# waterius-factory.net
KiCad netlist of a schematic drawn in EAGLE
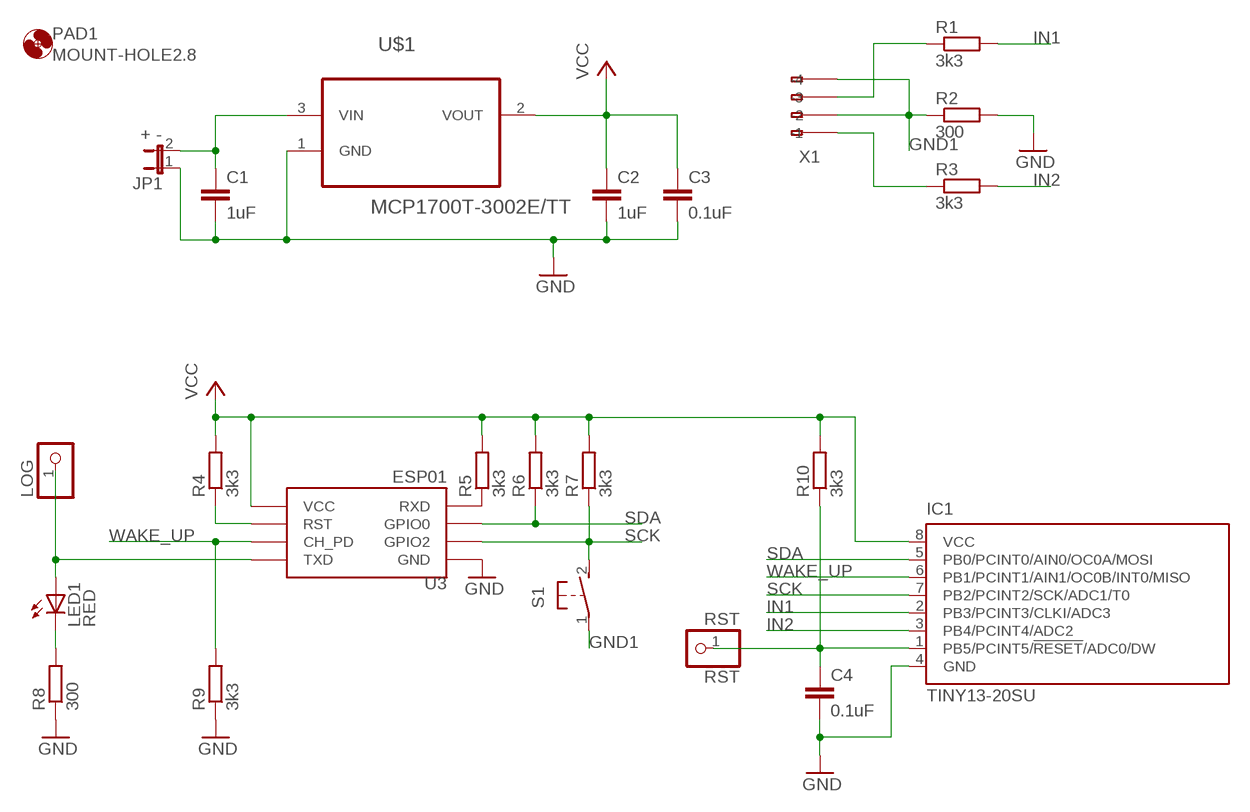
[diagram p0: schematic, sheet 1]

(export (version "E")
  (design (tool "Eeschema 10.0.6"))
  (components
    (comp (ref "C1")
      (value "1uF")
      (footprint "eagle-import:C0805")
      (libsource (lib "eagle-import") (part "C-EUC0805"))
    )
    (comp (ref "C2")
      (value "1uF")
      (footprint "eagle-import:C0805")
      (libsource (lib "eagle-import") (part "C-EUC0805"))
    )
    (comp (ref "C3")
      (value "0.1uF")
      (footprint "eagle-import:C0805")
      (libsource (lib "eagle-import") (part "C-EUC0805"))
    )
    (comp (ref "C4")
      (value "0.1uF")
      (footprint "eagle-import:C0805")
      (libsource (lib "eagle-import") (part "C-EUC0805"))
    )
    (comp (ref "IC1")
      (value "TINY13-20SU")
      (footprint "eagle-import:8S2")
      (fields (field (name "MPN") "ATTINY13-20SU"))
      (libsource (lib "eagle-import") (part "TINY13SU-20"))
    )
    (comp (ref "JP1")
      (value "+ -")
      (footprint "eagle-import:JP1")
      (libsource (lib "eagle-import") (part "JP1E"))
    )
    (comp (ref "LED1")
      (value "RED")
      (footprint "eagle-import:LED3MM")
      (libsource (lib "eagle-import") (part "LED3MM"))
    )
    (comp (ref "LOG")
      (value "PINHD-1X1")
      (footprint "eagle-import:1X01")
      (libsource (lib "eagle-import") (part "PINHD-1X1"))
    )
    (comp (ref "PAD1")
      (value "MOUNT-HOLE2.8")
      (footprint "eagle-import:2,8")
      (libsource (lib "eagle-import") (part "MOUNT-HOLE2.8"))
    )
    (comp (ref "R1")
      (value "3k3")
      (footprint "eagle-import:R0805")
      (libsource (lib "eagle-import") (part "R-EU_R0805"))
    )
    (comp (ref "R2")
      (value "300")
      (footprint "eagle-import:R0805")
      (libsource (lib "eagle-import") (part "R-EU_R0805"))
    )
    (comp (ref "R3")
      (value "3k3")
      (footprint "eagle-import:R0805")
      (libsource (lib "eagle-import") (part "R-EU_R0805"))
    )
    (comp (ref "R4")
      (value "3k3")
      (footprint "eagle-import:R0805")
      (libsource (lib "eagle-import") (part "R-EU_R0805"))
    )
    (comp (ref "R5")
      (value "3k3")
      (footprint "eagle-import:R0805")
      (libsource (lib "eagle-import") (part "R-EU_R0805"))
    )
    (comp (ref "R6")
      (value "3k3")
      (footprint "eagle-import:R0805")
      (libsource (lib "eagle-import") (part "R-EU_R0805"))
    )
    (comp (ref "R7")
      (value "3k3")
      (footprint "eagle-import:R0805")
      (libsource (lib "eagle-import") (part "R-EU_R0805"))
    )
    (comp (ref "R8")
      (value "300")
      (footprint "eagle-import:R0805")
      (libsource (lib "eagle-import") (part "R-EU_R0805"))
    )
    (comp (ref "R9")
      (value "3k3")
      (footprint "eagle-import:R0805")
      (libsource (lib "eagle-import") (part "R-EU_R0805"))
    )
    (comp (ref "R10")
      (value "3k3")
      (footprint "eagle-import:R0805")
      (libsource (lib "eagle-import") (part "R-EU_R0805"))
    )
    (comp (ref "RST")
      (value "RST")
      (footprint "eagle-import:1X01")
      (libsource (lib "eagle-import") (part "PINHD-1X1"))
    )
    (comp (ref "S1")
      (value "31-XX")
      (footprint "eagle-import:B3F-31XX")
      (fields (field (name "MPN") "B3F-3100"))
      (libsource (lib "eagle-import") (part "31-XX"))
    )
    (comp (ref "U$1")
      (value "MCP1700T-3002E/TT")
      (footprint "eagle-import:SOT95P237X112-3N")
      (libsource (lib "eagle-import") (part "MCP1700T-3002E/TT"))
    )
    (comp (ref "U3")
      (value "ESP01")
      (footprint "eagle-import:ESP01")
      (libsource (lib "eagle-import") (part "ESP01"))
    )
    (comp (ref "X1")
      (value "233-104")
      (footprint "eagle-import:233-104")
      (libsource (lib "eagle-import") (part "233-104"))
    )
  )
  (nets
    (net (code "1") (name "/GND1") (class "Default")
      (node (ref "R2") (pin "1") (pinfunction "1_1") (pintype "passive"))
      (node (ref "S1") (pin "1") (pinfunction "P_1") (pintype "passive"))
      (node (ref "X1") (pin "A2") (pinfunction "-2_A2") (pintype "passive"))
      (node (ref "X1") (pin "A4") (pinfunction "-4_A4") (pintype "passive"))
    )
    (net (code "2") (name "/IN1") (class "Default")
      (node (ref "IC1") (pin "2") (pinfunction "PB3/PCINT3/CLKI/ADC3_2") (pintype "bidirectional"))
      (node (ref "R1") (pin "2") (pinfunction "2_2") (pintype "passive"))
    )
    (net (code "3") (name "/IN2") (class "Default")
      (node (ref "IC1") (pin "3") (pinfunction "PB4/PCINT4/ADC2_3") (pintype "bidirectional"))
      (node (ref "R3") (pin "2") (pinfunction "2_2") (pintype "passive"))
    )
    (net (code "4") (name "/SCK") (class "Default")
      (node (ref "IC1") (pin "7") (pinfunction "PB2/PCINT2/SCK/ADC1/T0_7") (pintype "bidirectional"))
      (node (ref "R7") (pin "1") (pinfunction "1_1") (pintype "passive"))
      (node (ref "S1") (pin "2") (pinfunction "S_2") (pintype "passive"))
      (node (ref "U3") (pin "GPIO2") (pinfunction "GPIO2_GPIO2") (pintype "bidirectional"))
    )
    (net (code "5") (name "/SDA") (class "Default")
      (node (ref "IC1") (pin "5") (pinfunction "PB0/PCINT0/AIN0/OC0A/MOSI_5") (pintype "bidirectional"))
      (node (ref "R6") (pin "1") (pinfunction "1_1") (pintype "passive"))
      (node (ref "U3") (pin "GPIO0") (pinfunction "GPIO0_GPIO0") (pintype "bidirectional"))
    )
    (net (code "6") (name "/WAKE_UP") (class "Default")
      (node (ref "IC1") (pin "6") (pinfunction "PB1/PCINT1/AIN1/OC0B/INT0/MISO_6") (pintype "bidirectional"))
      (node (ref "R9") (pin "2") (pinfunction "2_2") (pintype "passive"))
      (node (ref "U3") (pin "CH_PD") (pinfunction "CH_PD_CH_PD") (pintype "bidirectional"))
    )
    (net (code "7") (name "GND") (class "Default")
      (node (ref "C1") (pin "2") (pinfunction "2_2") (pintype "passive"))
      (node (ref "C2") (pin "2") (pinfunction "2_2") (pintype "passive"))
      (node (ref "C3") (pin "2") (pinfunction "2_2") (pintype "passive"))
      (node (ref "C4") (pin "2") (pinfunction "2_2") (pintype "passive"))
      (node (ref "IC1") (pin "4") (pinfunction "GND_4") (pintype "power_in"))
      (node (ref "JP1") (pin "1") (pinfunction "1_1") (pintype "passive"))
      (node (ref "R2") (pin "2") (pinfunction "2_2") (pintype "passive"))
      (node (ref "R8") (pin "1") (pinfunction "1_1") (pintype "passive"))
      (node (ref "R9") (pin "1") (pinfunction "1_1") (pintype "passive"))
      (node (ref "U$1") (pin "1") (pinfunction "GND_1") (pintype "passive"))
      (node (ref "U3") (pin "GND") (pinfunction "GND_GND") (pintype "bidirectional"))
    )
    (net (code "8") (name "Net-(IC1-PB5{slash}PCINT5{slash}~{RESET}{slash}ADC0{slash}DW)") (class "Default")
      (node (ref "C4") (pin "1") (pinfunction "1_1") (pintype "passive"))
      (node (ref "IC1") (pin "1") (pinfunction "PB5/PCINT5/~{RESET}/ADC0/DW_1") (pintype "bidirectional"))
      (node (ref "R10") (pin "1") (pinfunction "1_1") (pintype "passive"))
      (node (ref "RST") (pin "1") (pinfunction "1_1") (pintype "passive"))
    )
    (net (code "9") (name "Net-(LED1-C)") (class "Default")
      (node (ref "LED1") (pin "K") (pinfunction "C_K") (pintype "passive"))
      (node (ref "R8") (pin "2") (pinfunction "2_2") (pintype "passive"))
    )
    (net (code "10") (name "Net-(R4-Pad1)") (class "Default")
      (node (ref "R4") (pin "1") (pinfunction "1_1") (pintype "passive"))
      (node (ref "U3") (pin "RST") (pinfunction "RST_RST") (pintype "bidirectional"))
    )
    (net (code "11") (name "Net-(U$1-VIN)") (class "Default")
      (node (ref "C1") (pin "1") (pinfunction "1_1") (pintype "passive"))
      (node (ref "JP1") (pin "2") (pinfunction "2_2") (pintype "passive"))
      (node (ref "U$1") (pin "3") (pinfunction "VIN_3") (pintype "input"))
    )
    (net (code "12") (name "Net-(U3-RXD)") (class "Default")
      (node (ref "R5") (pin "1") (pinfunction "1_1") (pintype "passive"))
      (node (ref "U3") (pin "RX") (pinfunction "RXD_RX") (pintype "bidirectional"))
    )
    (net (code "13") (name "Net-(U3-TXD)") (class "Default")
      (node (ref "LED1") (pin "A") (pinfunction "A_A") (pintype "passive"))
      (node (ref "LOG") (pin "1") (pinfunction "1_1") (pintype "passive"))
      (node (ref "U3") (pin "TX") (pinfunction "TXD_TX") (pintype "bidirectional"))
    )
    (net (code "14") (name "Net-(X1--1)") (class "Default")
      (node (ref "R3") (pin "1") (pinfunction "1_1") (pintype "passive"))
      (node (ref "X1") (pin "A1") (pinfunction "-1_A1") (pintype "passive"))
    )
    (net (code "15") (name "Net-(X1--3)") (class "Default")
      (node (ref "R1") (pin "1") (pinfunction "1_1") (pintype "passive"))
      (node (ref "X1") (pin "A3") (pinfunction "-3_A3") (pintype "passive"))
    )
    (net (code "16") (name "VCC") (class "Default")
      (node (ref "C2") (pin "1") (pinfunction "1_1") (pintype "passive"))
      (node (ref "C3") (pin "1") (pinfunction "1_1") (pintype "passive"))
      (node (ref "IC1") (pin "8") (pinfunction "VCC_8") (pintype "power_in"))
      (node (ref "R10") (pin "2") (pinfunction "2_2") (pintype "passive"))
      (node (ref "R4") (pin "2") (pinfunction "2_2") (pintype "passive"))
      (node (ref "R5") (pin "2") (pinfunction "2_2") (pintype "passive"))
      (node (ref "R6") (pin "2") (pinfunction "2_2") (pintype "passive"))
      (node (ref "R7") (pin "2") (pinfunction "2_2") (pintype "passive"))
      (node (ref "U$1") (pin "2") (pinfunction "VOUT_2") (pintype "output"))
      (node (ref "U3") (pin "VCC") (pinfunction "VCC_VCC") (pintype "bidirectional"))
    )
    (net (code "17") (name "unconnected-(X1-B-1-PadB1)") (class "Default")
      (node (ref "X1") (pin "B1") (pinfunction "B-1_B1") (pintype "passive"))
    )
    (net (code "18") (name "unconnected-(X1-B-2-PadB2)") (class "Default")
      (node (ref "X1") (pin "B2") (pinfunction "B-2_B2") (pintype "passive"))
    )
    (net (code "19") (name "unconnected-(X1-B-3-PadB3)") (class "Default")
      (node (ref "X1") (pin "B3") (pinfunction "B-3_B3") (pintype "passive"))
    )
    (net (code "20") (name "unconnected-(X1-B-4-PadB4)") (class "Default")
      (node (ref "X1") (pin "B4") (pinfunction "B-4_B4") (pintype "passive"))
    )
  )
)
